# Esquema_Display.net
KiCad netlist of a schematic drawn in Altium Designer
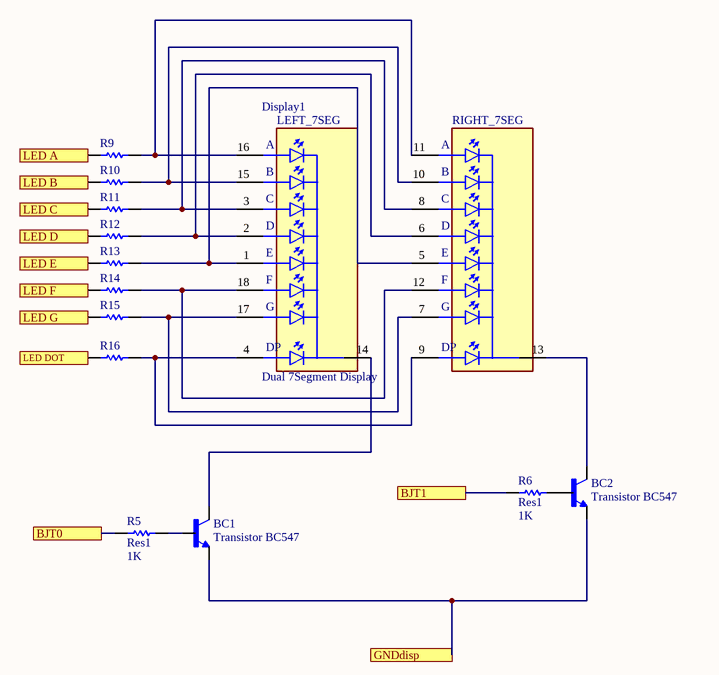
[diagram p0: Esquema_Display.SchDoc]

(export (version "E")
  (design (tool "Eeschema 10.0.6"))
  (components
    (comp (ref "BC1")
      (value "Transistor BC547")
      (footprint "Transistor BC547")
      (libsource (lib "myLibAltium") (part "Transistor BC547"))
    )
    (comp (ref "BC2")
      (value "Transistor BC547")
      (footprint "Transistor BC547")
      (libsource (lib "myLibAltium") (part "Transistor BC547"))
    )
    (comp (ref "Display1")
      (value "Dual 7Segment Display")
      (footprint "Dual Digit Display")
      (libsource (lib "myLibAltium") (part "Dual 7Segment Display"))
    )
    (comp (ref "R5")
      (value "Res1")
      (footprint "AXIAL-0.3")
      (description "Resistor")
      (fields (field (name "ALTIUM_VALUE") "1K") (field (name "PUBLISHER") "Altium Limited"))
      (libsource (lib "Miscellaneous Devices") (part "Res1"))
    )
    (comp (ref "R6")
      (value "Res1")
      (footprint "AXIAL-0.3")
      (description "Resistor")
      (fields (field (name "ALTIUM_VALUE") "1K") (field (name "PUBLISHER") "Altium Limited"))
      (libsource (lib "Miscellaneous Devices") (part "Res1"))
    )
    (comp (ref "R9")
      (value "Res1")
      (footprint "AXIAL-0.3")
      (description "Resistor")
      (fields (field (name "PUBLISHER") "Altium Limited"))
      (libsource (lib "Miscellaneous Devices") (part "Res1"))
    )
    (comp (ref "R10")
      (value "Res1")
      (footprint "AXIAL-0.3")
      (description "Resistor")
      (fields (field (name "PUBLISHER") "Altium Limited"))
      (libsource (lib "Miscellaneous Devices") (part "Res1"))
    )
    (comp (ref "R11")
      (value "Res1")
      (footprint "AXIAL-0.3")
      (description "Resistor")
      (fields (field (name "PUBLISHER") "Altium Limited"))
      (libsource (lib "Miscellaneous Devices") (part "Res1"))
    )
    (comp (ref "R12")
      (value "Res1")
      (footprint "AXIAL-0.3")
      (description "Resistor")
      (fields (field (name "PUBLISHER") "Altium Limited"))
      (libsource (lib "Miscellaneous Devices") (part "Res1"))
    )
    (comp (ref "R13")
      (value "Res1")
      (footprint "AXIAL-0.3")
      (description "Resistor")
      (fields (field (name "PUBLISHER") "Altium Limited"))
      (libsource (lib "Miscellaneous Devices") (part "Res1"))
    )
    (comp (ref "R14")
      (value "Res1")
      (footprint "AXIAL-0.3")
      (description "Resistor")
      (fields (field (name "PUBLISHER") "Altium Limited"))
      (libsource (lib "Miscellaneous Devices") (part "Res1"))
    )
    (comp (ref "R15")
      (value "Res1")
      (footprint "AXIAL-0.3")
      (description "Resistor")
      (fields (field (name "PUBLISHER") "Altium Limited"))
      (libsource (lib "Miscellaneous Devices") (part "Res1"))
    )
    (comp (ref "R16")
      (value "Res1")
      (footprint "AXIAL-0.3")
      (description "Resistor")
      (fields (field (name "PUBLISHER") "Altium Limited"))
      (libsource (lib "Miscellaneous Devices") (part "Res1"))
    )
  )
  (nets
    (net (code "1") (name "/BJT0") (class "Default")
      (node (ref "R5") (pin "1") (pinfunction "1_1") (pintype "passive"))
    )
    (net (code "2") (name "/BJT1") (class "Default")
      (node (ref "R6") (pin "1") (pinfunction "1_1") (pintype "passive"))
    )
    (net (code "3") (name "/GNDdisp") (class "Default")
      (node (ref "BC1") (pin "1") (pinfunction "E_1") (pintype "passive"))
      (node (ref "BC2") (pin "1") (pinfunction "E_1") (pintype "passive"))
    )
    (net (code "4") (name "/LED A") (class "Default")
      (node (ref "R9") (pin "1") (pinfunction "1_1") (pintype "passive"))
    )
    (net (code "5") (name "/LED B") (class "Default")
      (node (ref "R10") (pin "1") (pinfunction "1_1") (pintype "passive"))
    )
    (net (code "6") (name "/LED C") (class "Default")
      (node (ref "R11") (pin "1") (pinfunction "1_1") (pintype "passive"))
    )
    (net (code "7") (name "/LED D") (class "Default")
      (node (ref "R12") (pin "1") (pinfunction "1_1") (pintype "passive"))
    )
    (net (code "8") (name "/LED DOT") (class "Default")
      (node (ref "R16") (pin "1") (pinfunction "1_1") (pintype "passive"))
    )
    (net (code "9") (name "/LED E") (class "Default")
      (node (ref "R13") (pin "1") (pinfunction "1_1") (pintype "passive"))
    )
    (net (code "10") (name "/LED F") (class "Default")
      (node (ref "R14") (pin "1") (pinfunction "1_1") (pintype "passive"))
    )
    (net (code "11") (name "/LED G") (class "Default")
      (node (ref "R15") (pin "1") (pinfunction "1_1") (pintype "passive"))
    )
    (net (code "12") (name "Net-(BC1-B)") (class "Default")
      (node (ref "BC1") (pin "2") (pinfunction "B_2") (pintype "passive"))
      (node (ref "R5") (pin "2") (pinfunction "2_2") (pintype "passive"))
    )
    (net (code "13") (name "Net-(BC1-C)") (class "Default")
      (node (ref "BC1") (pin "3") (pinfunction "C_3") (pintype "passive"))
      (node (ref "Display1") (pin "14") (pinfunction "COM_1_14") (pintype "passive"))
    )
    (net (code "14") (name "Net-(BC2-B)") (class "Default")
      (node (ref "BC2") (pin "2") (pinfunction "B_2") (pintype "passive"))
      (node (ref "R6") (pin "2") (pinfunction "2_2") (pintype "passive"))
    )
    (net (code "15") (name "Net-(BC2-C)") (class "Default")
      (node (ref "BC2") (pin "3") (pinfunction "C_3") (pintype "passive"))
      (node (ref "Display1") (pin "13") (pinfunction "COM_2_13") (pintype "passive"))
    )
    (net (code "16") (name "Net-(Display1-A_1)") (class "Default")
      (node (ref "Display1") (pin "11") (pinfunction "A_2_11") (pintype "passive"))
      (node (ref "Display1") (pin "16") (pinfunction "A_1_16") (pintype "passive"))
      (node (ref "R9") (pin "2") (pinfunction "2_2") (pintype "passive"))
    )
    (net (code "17") (name "Net-(Display1-B_1)") (class "Default")
      (node (ref "Display1") (pin "10") (pinfunction "B_2_10") (pintype "passive"))
      (node (ref "Display1") (pin "15") (pinfunction "B_1_15") (pintype "passive"))
      (node (ref "R10") (pin "2") (pinfunction "2_2") (pintype "passive"))
    )
    (net (code "18") (name "Net-(Display1-C_1)") (class "Default")
      (node (ref "Display1") (pin "3") (pinfunction "C_1_3") (pintype "passive"))
      (node (ref "Display1") (pin "8") (pinfunction "C_2_8") (pintype "passive"))
      (node (ref "R11") (pin "2") (pinfunction "2_2") (pintype "passive"))
    )
    (net (code "19") (name "Net-(Display1-DP_1)") (class "Default")
      (node (ref "Display1") (pin "4") (pinfunction "DP_1_4") (pintype "passive"))
      (node (ref "Display1") (pin "9") (pinfunction "DP_2_9") (pintype "passive"))
      (node (ref "R16") (pin "2") (pinfunction "2_2") (pintype "passive"))
    )
    (net (code "20") (name "Net-(Display1-D_1)") (class "Default")
      (node (ref "Display1") (pin "2") (pinfunction "D_1_2") (pintype "passive"))
      (node (ref "Display1") (pin "6") (pinfunction "D_2_6") (pintype "passive"))
      (node (ref "R12") (pin "2") (pinfunction "2_2") (pintype "passive"))
    )
    (net (code "21") (name "Net-(Display1-E_1)") (class "Default")
      (node (ref "Display1") (pin "1") (pinfunction "E_1_1") (pintype "passive"))
      (node (ref "Display1") (pin "5") (pinfunction "E_2_5") (pintype "passive"))
      (node (ref "R13") (pin "2") (pinfunction "2_2") (pintype "passive"))
    )
    (net (code "22") (name "Net-(Display1-F_1)") (class "Default")
      (node (ref "Display1") (pin "12") (pinfunction "F_2_12") (pintype "passive"))
      (node (ref "Display1") (pin "18") (pinfunction "F_1_18") (pintype "passive"))
      (node (ref "R14") (pin "2") (pinfunction "2_2") (pintype "passive"))
    )
    (net (code "23") (name "Net-(Display1-G_1)") (class "Default")
      (node (ref "Display1") (pin "17") (pinfunction "G_1_17") (pintype "passive"))
      (node (ref "Display1") (pin "7") (pinfunction "G_2_7") (pintype "passive"))
      (node (ref "R15") (pin "2") (pinfunction "2_2") (pintype "passive"))
    )
  )
)
